# SCH_Display-LCD_EasyEDA.net
KiCad netlist of a schematic drawn in EasyEDA
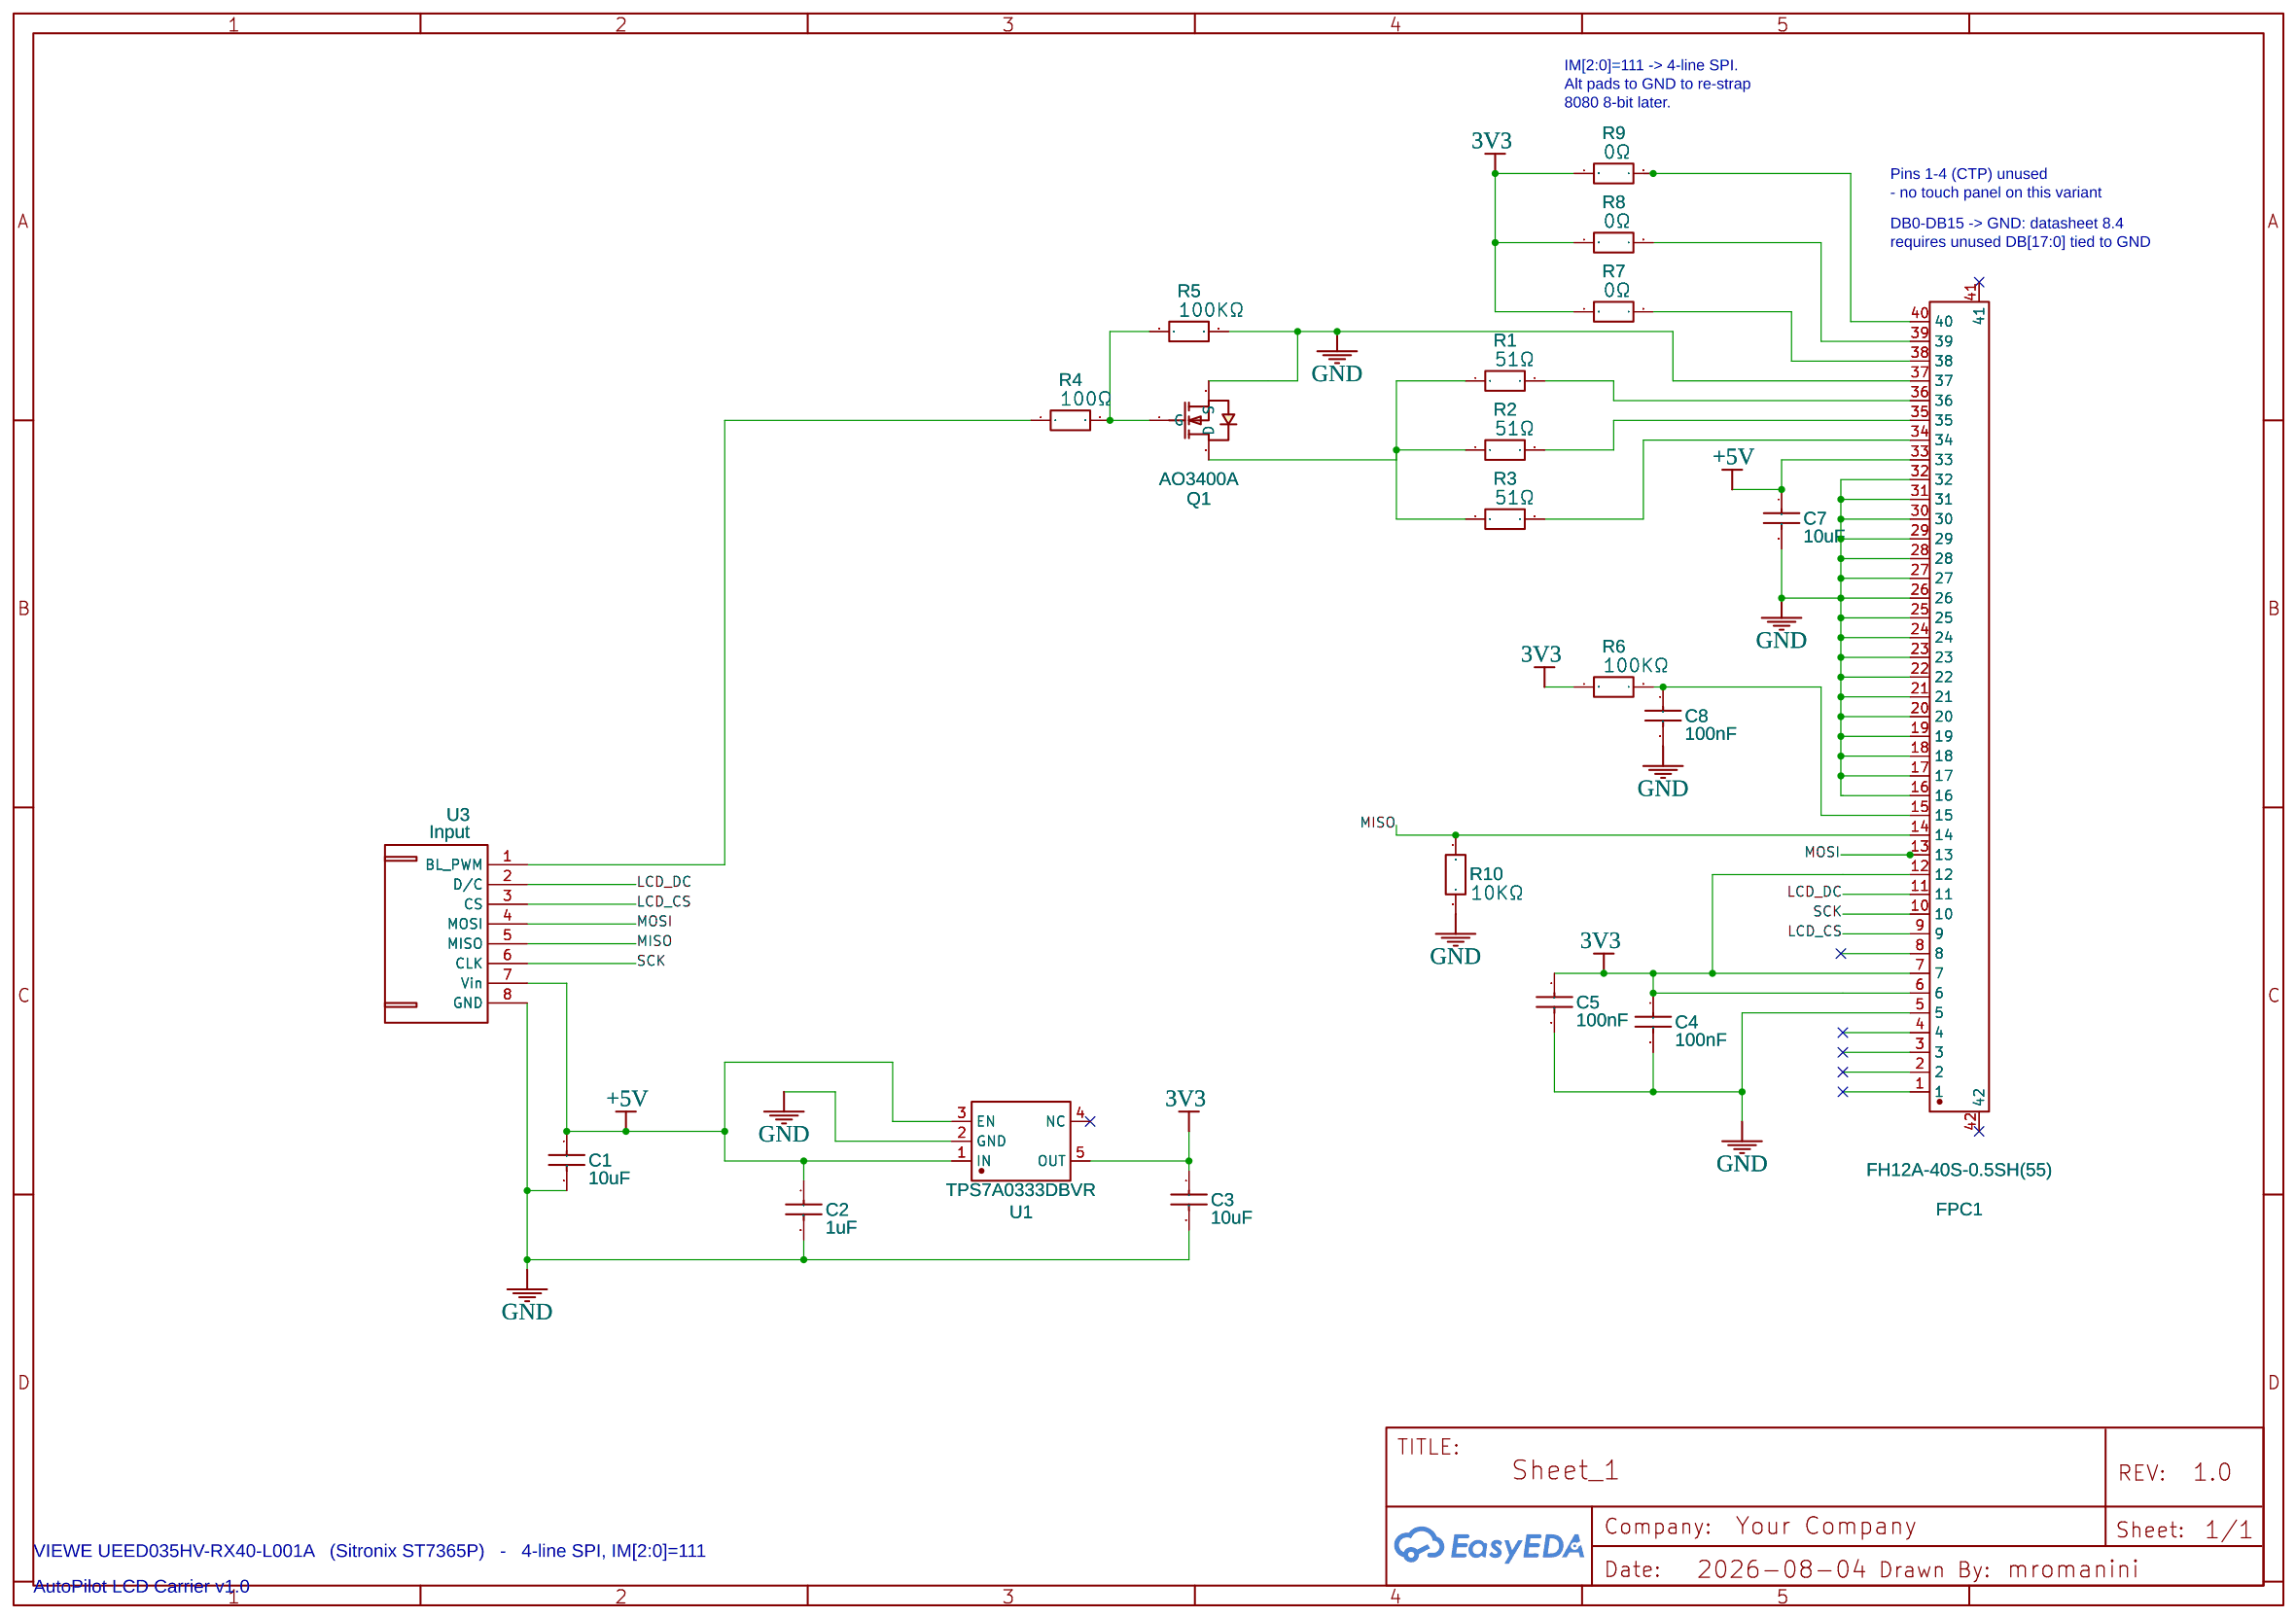
[diagram p0: schematic sheet]

(export (version "E")
  (design (tool "Eeschema 10.0.6"))
  (components
    (comp (ref "C1")
      (value "10uF")
      (fields (field (name "Manufacturer Part") "Capacitor_Ceramic"))
      (libsource (lib "") (part "Capacitor_Ceramic"))
    )
    (comp (ref "C2")
      (value "1uF")
      (fields (field (name "Manufacturer Part") "Capacitor_Ceramic"))
      (libsource (lib "") (part "Capacitor_Ceramic"))
    )
    (comp (ref "C3")
      (value "10uF")
      (fields (field (name "Manufacturer Part") "Capacitor_Ceramic"))
      (libsource (lib "") (part "Capacitor_Ceramic"))
    )
    (comp (ref "C4")
      (value "100nF")
      (fields (field (name "Manufacturer Part") "Capacitor_Ceramic"))
      (libsource (lib "") (part "Capacitor_Ceramic"))
    )
    (comp (ref "C5")
      (value "100nF")
      (fields (field (name "Manufacturer Part") "Capacitor_Ceramic"))
      (libsource (lib "") (part "Capacitor_Ceramic"))
    )
    (comp (ref "C7")
      (value "10uF")
      (fields (field (name "Manufacturer Part") "Capacitor_Ceramic"))
      (libsource (lib "") (part "Capacitor_Ceramic"))
    )
    (comp (ref "C8")
      (value "100nF")
      (fields (field (name "Manufacturer Part") "Capacitor_Ceramic"))
      (libsource (lib "") (part "Capacitor_Ceramic"))
    )
    (comp (ref "FPC1")
      (value "FH12A-40S-0.5SH(55)")
      (fields (field (name "Manufacturer") "HRS(广濑)"))
      (libsource (lib "") (part "FH12A-40S-0.5SH(55)"))
    )
    (comp (ref "Q1")
      (value "AO3400A")
      (fields (field (name "Manufacturer") "AOS"))
      (libsource (lib "") (part "AO3400A"))
    )
    (comp (ref "R1") (value "51Ω") (libsource (lib "") (part "1w resistor")))
    (comp (ref "R2") (value "51Ω") (libsource (lib "") (part "1w resistor")))
    (comp (ref "R3") (value "51Ω") (libsource (lib "") (part "1w resistor")))
    (comp (ref "R4") (value "100Ω") (libsource (lib "") (part "1w resistor")))
    (comp (ref "R5") (value "100KΩ") (libsource (lib "") (part "1w resistor")))
    (comp (ref "R6") (value "100KΩ") (libsource (lib "") (part "1w resistor")))
    (comp (ref "R7") (value "0Ω") (libsource (lib "") (part "1w resistor")))
    (comp (ref "R8") (value "0Ω") (libsource (lib "") (part "1w resistor")))
    (comp (ref "R9") (value "0Ω") (libsource (lib "") (part "1w resistor")))
    (comp (ref "R10") (value "10KΩ") (libsource (lib "") (part "1w resistor_1")))
    (comp (ref "U1")
      (value "TPS7A0333DBVR")
      (fields (field (name "Manufacturer") "TI(德州仪器)"))
      (libsource (lib "") (part "TPS7A0333DBVR"))
    )
    (comp (ref "U3") (value "Input") (libsource (lib "") (part "JST-XH-8-Pin")))
  )
  (nets
    (net (code "1") (name "+5V") (class "Default")
      (node (ref "C1") (pin "1") (pinfunction "1_1") (pintype "unspecified"))
      (node (ref "C2") (pin "1") (pinfunction "1_1") (pintype "unspecified"))
      (node (ref "C7") (pin "1") (pinfunction "1_1") (pintype "unspecified"))
      (node (ref "FPC1") (pin "33") (pinfunction "33_33") (pintype "unspecified"))
      (node (ref "U1") (pin "1") (pinfunction "IN_1") (pintype "unspecified"))
      (node (ref "U1") (pin "3") (pinfunction "EN_3") (pintype "unspecified"))
      (node (ref "U3") (pin "7") (pinfunction "Vin_7") (pintype "unspecified"))
    )
    (net (code "2") (name "/LCD_CS") (class "Default")
      (node (ref "FPC1") (pin "9") (pinfunction "9_9") (pintype "unspecified"))
      (node (ref "U3") (pin "3") (pinfunction "CS_3") (pintype "unspecified"))
    )
    (net (code "3") (name "/LCD_DC") (class "Default")
      (node (ref "FPC1") (pin "11") (pinfunction "11_11") (pintype "unspecified"))
      (node (ref "U3") (pin "2") (pinfunction "D/C_2") (pintype "unspecified"))
    )
    (net (code "4") (name "/MISO") (class "Default")
      (node (ref "FPC1") (pin "14") (pinfunction "14_14") (pintype "unspecified"))
      (node (ref "R10") (pin "1") (pinfunction "2_1") (pintype "unspecified"))
      (node (ref "U3") (pin "5") (pinfunction "MISO_5") (pintype "unspecified"))
    )
    (net (code "5") (name "/MOSI") (class "Default")
      (node (ref "FPC1") (pin "13") (pinfunction "13_13") (pintype "unspecified"))
      (node (ref "U3") (pin "4") (pinfunction "MOSI_4") (pintype "unspecified"))
    )
    (net (code "6") (name "/SCK") (class "Default")
      (node (ref "FPC1") (pin "10") (pinfunction "10_10") (pintype "unspecified"))
      (node (ref "U3") (pin "6") (pinfunction "CLK_6") (pintype "unspecified"))
    )
    (net (code "7") (name "3V3") (class "Default")
      (node (ref "C3") (pin "1") (pinfunction "1_1") (pintype "unspecified"))
      (node (ref "C4") (pin "1") (pinfunction "1_1") (pintype "unspecified"))
      (node (ref "C5") (pin "1") (pinfunction "1_1") (pintype "unspecified"))
      (node (ref "FPC1") (pin "12") (pinfunction "12_12") (pintype "unspecified"))
      (node (ref "FPC1") (pin "6") (pinfunction "6_6") (pintype "unspecified"))
      (node (ref "FPC1") (pin "7") (pinfunction "7_7") (pintype "unspecified"))
      (node (ref "R6") (pin "1") (pinfunction "2_1") (pintype "unspecified"))
      (node (ref "R7") (pin "1") (pinfunction "2_1") (pintype "unspecified"))
      (node (ref "R8") (pin "1") (pinfunction "2_1") (pintype "unspecified"))
      (node (ref "R9") (pin "1") (pinfunction "2_1") (pintype "unspecified"))
      (node (ref "U1") (pin "5") (pinfunction "OUT_5") (pintype "unspecified"))
    )
    (net (code "8") (name "GND") (class "Default")
      (node (ref "C1") (pin "2") (pinfunction "2_2") (pintype "unspecified"))
      (node (ref "C2") (pin "2") (pinfunction "2_2") (pintype "unspecified"))
      (node (ref "C3") (pin "2") (pinfunction "2_2") (pintype "unspecified"))
      (node (ref "C4") (pin "2") (pinfunction "2_2") (pintype "unspecified"))
      (node (ref "C5") (pin "2") (pinfunction "2_2") (pintype "unspecified"))
      (node (ref "C7") (pin "2") (pinfunction "2_2") (pintype "unspecified"))
      (node (ref "C8") (pin "2") (pinfunction "2_2") (pintype "unspecified"))
      (node (ref "FPC1") (pin "16") (pinfunction "16_16") (pintype "unspecified"))
      (node (ref "FPC1") (pin "17") (pinfunction "17_17") (pintype "unspecified"))
      (node (ref "FPC1") (pin "18") (pinfunction "18_18") (pintype "unspecified"))
      (node (ref "FPC1") (pin "19") (pinfunction "19_19") (pintype "unspecified"))
      (node (ref "FPC1") (pin "20") (pinfunction "20_20") (pintype "unspecified"))
      (node (ref "FPC1") (pin "21") (pinfunction "21_21") (pintype "unspecified"))
      (node (ref "FPC1") (pin "22") (pinfunction "22_22") (pintype "unspecified"))
      (node (ref "FPC1") (pin "23") (pinfunction "23_23") (pintype "unspecified"))
      (node (ref "FPC1") (pin "24") (pinfunction "24_24") (pintype "unspecified"))
      (node (ref "FPC1") (pin "25") (pinfunction "25_25") (pintype "unspecified"))
      (node (ref "FPC1") (pin "26") (pinfunction "26_26") (pintype "unspecified"))
      (node (ref "FPC1") (pin "27") (pinfunction "27_27") (pintype "unspecified"))
      (node (ref "FPC1") (pin "28") (pinfunction "28_28") (pintype "unspecified"))
      (node (ref "FPC1") (pin "29") (pinfunction "29_29") (pintype "unspecified"))
      (node (ref "FPC1") (pin "30") (pinfunction "30_30") (pintype "unspecified"))
      (node (ref "FPC1") (pin "31") (pinfunction "31_31") (pintype "unspecified"))
      (node (ref "FPC1") (pin "32") (pinfunction "32_32") (pintype "unspecified"))
      (node (ref "FPC1") (pin "37") (pinfunction "37_37") (pintype "unspecified"))
      (node (ref "FPC1") (pin "5") (pinfunction "5_5") (pintype "unspecified"))
      (node (ref "Q1") (pin "2") (pinfunction "S_2") (pintype "unspecified"))
      (node (ref "R10") (pin "2") (pinfunction "1_2") (pintype "unspecified"))
      (node (ref "R5") (pin "2") (pinfunction "1_2") (pintype "unspecified"))
      (node (ref "U1") (pin "2") (pinfunction "GND_2") (pintype "unspecified"))
      (node (ref "U3") (pin "8") (pinfunction "GND_8") (pintype "unspecified"))
    )
    (net (code "9") (name "Net-(Q1-D)") (class "Default")
      (node (ref "Q1") (pin "3") (pinfunction "D_3") (pintype "unspecified"))
      (node (ref "R1") (pin "1") (pinfunction "2_1") (pintype "unspecified"))
      (node (ref "R2") (pin "1") (pinfunction "2_1") (pintype "unspecified"))
      (node (ref "R3") (pin "1") (pinfunction "2_1") (pintype "unspecified"))
    )
    (net (code "10") (name "Net-(Q1-G)") (class "Default")
      (node (ref "Q1") (pin "1") (pinfunction "G_1") (pintype "unspecified"))
      (node (ref "R4") (pin "2") (pinfunction "1_2") (pintype "unspecified"))
      (node (ref "R5") (pin "1") (pinfunction "2_1") (pintype "unspecified"))
    )
    (net (code "11") (name "Net-(R1-1)") (class "Default")
      (node (ref "FPC1") (pin "36") (pinfunction "36_36") (pintype "unspecified"))
      (node (ref "R1") (pin "2") (pinfunction "1_2") (pintype "unspecified"))
    )
    (net (code "12") (name "Net-(R2-1)") (class "Default")
      (node (ref "FPC1") (pin "35") (pinfunction "35_35") (pintype "unspecified"))
      (node (ref "R2") (pin "2") (pinfunction "1_2") (pintype "unspecified"))
    )
    (net (code "13") (name "Net-(R3-1)") (class "Default")
      (node (ref "FPC1") (pin "34") (pinfunction "34_34") (pintype "unspecified"))
      (node (ref "R3") (pin "2") (pinfunction "1_2") (pintype "unspecified"))
    )
    (net (code "14") (name "Net-(R4-2)") (class "Default")
      (node (ref "R4") (pin "1") (pinfunction "2_1") (pintype "unspecified"))
      (node (ref "U3") (pin "1") (pinfunction "BL_PWM_1") (pintype "unspecified"))
    )
    (net (code "15") (name "Net-(R6-1)") (class "Default")
      (node (ref "C8") (pin "1") (pinfunction "1_1") (pintype "unspecified"))
      (node (ref "FPC1") (pin "15") (pinfunction "15_15") (pintype "unspecified"))
      (node (ref "R6") (pin "2") (pinfunction "1_2") (pintype "unspecified"))
    )
    (net (code "16") (name "Net-(R7-1)") (class "Default")
      (node (ref "FPC1") (pin "38") (pinfunction "38_38") (pintype "unspecified"))
      (node (ref "R7") (pin "2") (pinfunction "1_2") (pintype "unspecified"))
    )
    (net (code "17") (name "Net-(R8-1)") (class "Default")
      (node (ref "FPC1") (pin "39") (pinfunction "39_39") (pintype "unspecified"))
      (node (ref "R8") (pin "2") (pinfunction "1_2") (pintype "unspecified"))
    )
    (net (code "18") (name "Net-(R9-1)") (class "Default")
      (node (ref "FPC1") (pin "40") (pinfunction "40_40") (pintype "unspecified"))
      (node (ref "R9") (pin "2") (pinfunction "1_2") (pintype "unspecified"))
    )
    (net (code "19") (name "unconnected-(FPC1-Pad1)") (class "Default")
      (node (ref "FPC1") (pin "1") (pinfunction "1_1") (pintype "unspecified+no_connect"))
    )
    (net (code "20") (name "unconnected-(FPC1-Pad2)") (class "Default")
      (node (ref "FPC1") (pin "2") (pinfunction "2_2") (pintype "unspecified+no_connect"))
    )
    (net (code "21") (name "unconnected-(FPC1-Pad3)") (class "Default")
      (node (ref "FPC1") (pin "3") (pinfunction "3_3") (pintype "unspecified+no_connect"))
    )
    (net (code "22") (name "unconnected-(FPC1-Pad4)") (class "Default")
      (node (ref "FPC1") (pin "4") (pinfunction "4_4") (pintype "unspecified+no_connect"))
    )
    (net (code "23") (name "unconnected-(FPC1-Pad8)") (class "Default")
      (node (ref "FPC1") (pin "8") (pinfunction "8_8") (pintype "unspecified+no_connect"))
    )
    (net (code "24") (name "unconnected-(FPC1-Pad41)") (class "Default")
      (node (ref "FPC1") (pin "41") (pinfunction "41_41") (pintype "unspecified+no_connect"))
    )
    (net (code "25") (name "unconnected-(FPC1-Pad42)") (class "Default")
      (node (ref "FPC1") (pin "42") (pinfunction "42_42") (pintype "unspecified+no_connect"))
    )
    (net (code "26") (name "unconnected-(U1-NC-Pad4)") (class "Default")
      (node (ref "U1") (pin "4") (pinfunction "NC_4") (pintype "unspecified+no_connect"))
    )
  )
)
